# schematic.net
KiCad netlist of a schematic drawn in EAGLE
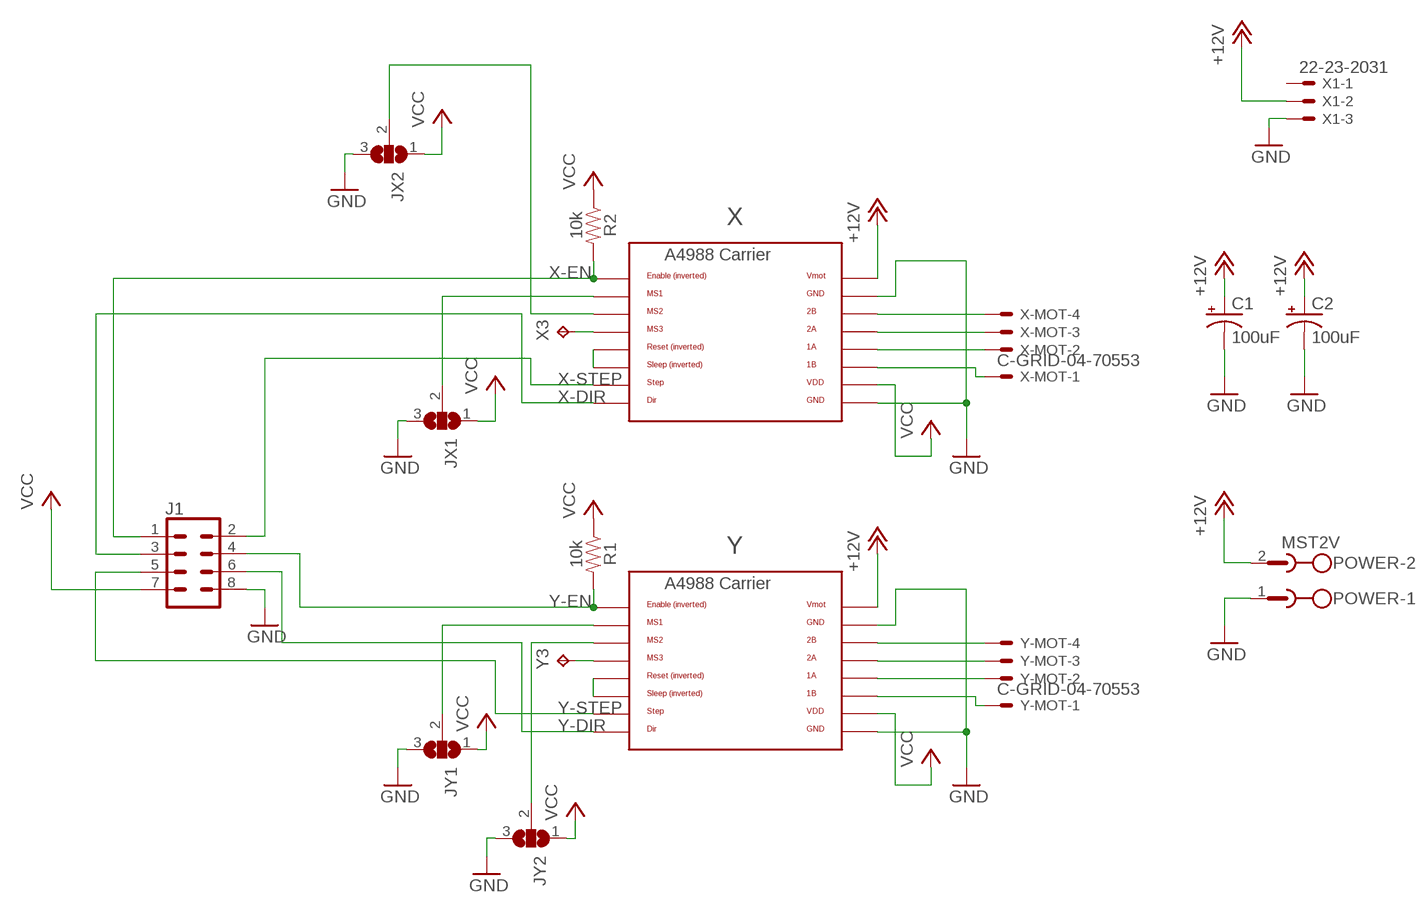
[diagram p0: schematic, sheet 1]

(export (version "E")
  (design (tool "Eeschema 10.0.6"))
  (components
    (comp (ref "C1")
      (value "100uF")
      (footprint "eagle-import:CPOL-RADIAL-2.5MM-6.5MM")
      (libsource (lib "eagle-import") (part "100UF-POLAR-RADIAL-2.5MM-25V-20%"))
    )
    (comp (ref "C2")
      (value "100uF")
      (footprint "eagle-import:CPOL-RADIAL-2.5MM-6.5MM")
      (libsource (lib "eagle-import") (part "100UF-POLAR-RADIAL-2.5MM-25V-20%"))
    )
    (comp (ref "J1")
      (value "CONN_04X2")
      (footprint "eagle-import:2X4")
      (libsource (lib "eagle-import") (part "CONN_04X2"))
    )
    (comp (ref "JX1")
      (value "SJ2W")
      (footprint "eagle-import:SJ_2")
      (libsource (lib "eagle-import") (part "SJ2W"))
    )
    (comp (ref "JX2")
      (value "SJ2W")
      (footprint "eagle-import:SJ_2")
      (libsource (lib "eagle-import") (part "SJ2W"))
    )
    (comp (ref "JY1")
      (value "SJ2W")
      (footprint "eagle-import:SJ_2")
      (libsource (lib "eagle-import") (part "SJ2W"))
    )
    (comp (ref "JY2")
      (value "SJ2W")
      (footprint "eagle-import:SJ_2")
      (libsource (lib "eagle-import") (part "SJ2W"))
    )
    (comp (ref "POWER")
      (value "MST2V")
      (footprint "eagle-import:MSTBV2")
      (libsource (lib "eagle-import") (part "MST2V"))
    )
    (comp (ref "R1")
      (value "10k")
      (footprint "eagle-import:AXIAL-0.3")
      (libsource (lib "eagle-import") (part "10KOHM-HORIZ-1/4W-1%"))
    )
    (comp (ref "R2")
      (value "10k")
      (footprint "eagle-import:AXIAL-0.3")
      (libsource (lib "eagle-import") (part "10KOHM-HORIZ-1/4W-1%"))
    )
    (comp (ref "U$1")
      (value "A4988BREAKOUT")
      (footprint "eagle-import:A4988BREAKOUT")
      (libsource (lib "eagle-import") (part "A4988BREAKOUT"))
    )
    (comp (ref "U$4")
      (value "A4988BREAKOUT")
      (footprint "eagle-import:A4988BREAKOUT")
      (libsource (lib "eagle-import") (part "A4988BREAKOUT"))
    )
    (comp (ref "X-MOT")
      (value "C-GRID-04-70553")
      (footprint "eagle-import:70553-04")
      (libsource (lib "eagle-import") (part "C-GRID-04-70553"))
    )
    (comp (ref "X1")
      (value "22-23-2031")
      (footprint "eagle-import:22-23-2031")
      (fields (field (name "MF") "MOLEX"))
      (libsource (lib "eagle-import") (part "22-23-2031"))
    )
    (comp (ref "X3")
      (value "TPB1,27")
      (footprint "eagle-import:B1,27")
      (libsource (lib "eagle-import") (part "TPB1,27"))
    )
    (comp (ref "Y-MOT")
      (value "C-GRID-04-70553")
      (footprint "eagle-import:70553-04")
      (libsource (lib "eagle-import") (part "C-GRID-04-70553"))
    )
    (comp (ref "Y3")
      (value "TPB1,27")
      (footprint "eagle-import:B1,27")
      (libsource (lib "eagle-import") (part "TPB1,27"))
    )
  )
  (nets
    (net (code "1") (name "+12V") (class "Default")
      (node (ref "C1") (pin "1") (pinfunction "+_1") (pintype "passive"))
      (node (ref "C2") (pin "1") (pinfunction "+_1") (pintype "passive"))
      (node (ref "POWER") (pin "2") (pinfunction "1_2") (pintype "passive"))
      (node (ref "U$1") (pin "VMOT") (pinfunction "VMOT_VMOT") (pintype "power_in"))
      (node (ref "U$4") (pin "VMOT") (pinfunction "VMOT_VMOT") (pintype "power_in"))
      (node (ref "X1") (pin "2") (pinfunction "S_2") (pintype "passive"))
    )
    (net (code "2") (name "/X-DIR") (class "Default")
      (node (ref "J1") (pin "3") (pinfunction "3_3") (pintype "passive"))
      (node (ref "U$1") (pin "DIR") (pinfunction "DIR_DIR") (pintype "input"))
    )
    (net (code "3") (name "/X-EN") (class "Default")
      (node (ref "J1") (pin "1") (pinfunction "1_1") (pintype "passive"))
      (node (ref "R2") (pin "P$2") (pinfunction "2_P$2") (pintype "passive"))
      (node (ref "U$1") (pin "EN") (pinfunction "EN_EN") (pintype "input"))
    )
    (net (code "4") (name "/X-STEP") (class "Default")
      (node (ref "J1") (pin "2") (pinfunction "2_2") (pintype "passive"))
      (node (ref "U$1") (pin "STEP") (pinfunction "STEP_STEP") (pintype "input"))
    )
    (net (code "5") (name "/Y-DIR") (class "Default")
      (node (ref "J1") (pin "6") (pinfunction "6_6") (pintype "passive"))
      (node (ref "U$4") (pin "DIR") (pinfunction "DIR_DIR") (pintype "input"))
    )
    (net (code "6") (name "/Y-EN") (class "Default")
      (node (ref "J1") (pin "4") (pinfunction "4_4") (pintype "passive"))
      (node (ref "R1") (pin "P$2") (pinfunction "2_P$2") (pintype "passive"))
      (node (ref "U$4") (pin "EN") (pinfunction "EN_EN") (pintype "input"))
    )
    (net (code "7") (name "/Y-STEP") (class "Default")
      (node (ref "J1") (pin "5") (pinfunction "5_5") (pintype "passive"))
      (node (ref "U$4") (pin "STEP") (pinfunction "STEP_STEP") (pintype "input"))
    )
    (net (code "8") (name "GND") (class "Default")
      (node (ref "C1") (pin "2") (pinfunction "-_2") (pintype "passive"))
      (node (ref "C2") (pin "2") (pinfunction "-_2") (pintype "passive"))
      (node (ref "J1") (pin "8") (pinfunction "8_8") (pintype "passive"))
      (node (ref "JX1") (pin "3") (pinfunction "3_3") (pintype "passive"))
      (node (ref "JX2") (pin "3") (pinfunction "3_3") (pintype "passive"))
      (node (ref "JY1") (pin "3") (pinfunction "3_3") (pintype "passive"))
      (node (ref "JY2") (pin "3") (pinfunction "3_3") (pintype "passive"))
      (node (ref "POWER") (pin "1") (pinfunction "1_1") (pintype "passive"))
      (node (ref "U$1") (pin "GND") (pinfunction "GND_GND") (pintype "power_in"))
      (node (ref "U$1") (pin "GND@0") (pinfunction "GND_GND@0") (pintype "power_in"))
      (node (ref "U$4") (pin "GND") (pinfunction "GND_GND") (pintype "power_in"))
      (node (ref "U$4") (pin "GND@0") (pinfunction "GND_GND@0") (pintype "power_in"))
      (node (ref "X1") (pin "3") (pinfunction "S_3") (pintype "passive"))
    )
    (net (code "9") (name "Net-(JX1-Pad2)") (class "Default")
      (node (ref "JX1") (pin "2") (pinfunction "2_2") (pintype "passive"))
      (node (ref "U$1") (pin "MS1") (pinfunction "MS1_MS1") (pintype "input"))
    )
    (net (code "10") (name "Net-(JX2-Pad2)") (class "Default")
      (node (ref "JX2") (pin "2") (pinfunction "2_2") (pintype "passive"))
      (node (ref "U$1") (pin "MS2") (pinfunction "MS2_MS2") (pintype "input"))
    )
    (net (code "11") (name "Net-(JY1-Pad2)") (class "Default")
      (node (ref "JY1") (pin "2") (pinfunction "2_2") (pintype "passive"))
      (node (ref "U$4") (pin "MS1") (pinfunction "MS1_MS1") (pintype "input"))
    )
    (net (code "12") (name "Net-(JY2-Pad2)") (class "Default")
      (node (ref "JY2") (pin "2") (pinfunction "2_2") (pintype "passive"))
      (node (ref "U$4") (pin "MS2") (pinfunction "MS2_MS2") (pintype "input"))
    )
    (net (code "13") (name "Net-(U$1-PadMS3)") (class "Default")
      (node (ref "U$1") (pin "MS3") (pinfunction "MS3_MS3") (pintype "input"))
      (node (ref "X3") (pin "TP") (pinfunction "TP_TP") (pintype "input"))
    )
    (net (code "14") (name "Net-(U$1-SLEEP)") (class "Default")
      (node (ref "U$1") (pin "RST") (pinfunction "RST_RST") (pintype "input"))
      (node (ref "U$1") (pin "SLP") (pinfunction "SLEEP_SLP") (pintype "input"))
    )
    (net (code "15") (name "Net-(U$4-PadMS3)") (class "Default")
      (node (ref "U$4") (pin "MS3") (pinfunction "MS3_MS3") (pintype "input"))
      (node (ref "Y3") (pin "TP") (pinfunction "TP_TP") (pintype "input"))
    )
    (net (code "16") (name "Net-(U$4-SLEEP)") (class "Default")
      (node (ref "U$4") (pin "RST") (pinfunction "RST_RST") (pintype "input"))
      (node (ref "U$4") (pin "SLP") (pinfunction "SLEEP_SLP") (pintype "input"))
    )
    (net (code "17") (name "Net-(X-MOTA-S)") (class "Default")
      (node (ref "U$1") (pin "1B") (pinfunction "1B_1B") (pintype "output"))
      (node (ref "X-MOT") (pin "1") (pinfunction "S_1") (pintype "passive"))
    )
    (net (code "18") (name "Net-(X-MOTB-S)") (class "Default")
      (node (ref "U$1") (pin "1A") (pinfunction "1A_1A") (pintype "output"))
      (node (ref "X-MOT") (pin "2") (pinfunction "S_2") (pintype "passive"))
    )
    (net (code "19") (name "Net-(X-MOTC-S)") (class "Default")
      (node (ref "U$1") (pin "2A") (pinfunction "2A_2A") (pintype "output"))
      (node (ref "X-MOT") (pin "3") (pinfunction "S_3") (pintype "passive"))
    )
    (net (code "20") (name "Net-(X-MOTD-S)") (class "Default")
      (node (ref "U$1") (pin "2B") (pinfunction "2B_2B") (pintype "output"))
      (node (ref "X-MOT") (pin "4") (pinfunction "S_4") (pintype "passive"))
    )
    (net (code "21") (name "Net-(Y-MOTA-S)") (class "Default")
      (node (ref "U$4") (pin "1B") (pinfunction "1B_1B") (pintype "output"))
      (node (ref "Y-MOT") (pin "1") (pinfunction "S_1") (pintype "passive"))
    )
    (net (code "22") (name "Net-(Y-MOTB-S)") (class "Default")
      (node (ref "U$4") (pin "1A") (pinfunction "1A_1A") (pintype "output"))
      (node (ref "Y-MOT") (pin "2") (pinfunction "S_2") (pintype "passive"))
    )
    (net (code "23") (name "Net-(Y-MOTC-S)") (class "Default")
      (node (ref "U$4") (pin "2A") (pinfunction "2A_2A") (pintype "output"))
      (node (ref "Y-MOT") (pin "3") (pinfunction "S_3") (pintype "passive"))
    )
    (net (code "24") (name "Net-(Y-MOTD-S)") (class "Default")
      (node (ref "U$4") (pin "2B") (pinfunction "2B_2B") (pintype "output"))
      (node (ref "Y-MOT") (pin "4") (pinfunction "S_4") (pintype "passive"))
    )
    (net (code "25") (name "VCC") (class "Default")
      (node (ref "J1") (pin "7") (pinfunction "7_7") (pintype "passive"))
      (node (ref "JX1") (pin "1") (pinfunction "1_1") (pintype "passive"))
      (node (ref "JX2") (pin "1") (pinfunction "1_1") (pintype "passive"))
      (node (ref "JY1") (pin "1") (pinfunction "1_1") (pintype "passive"))
      (node (ref "JY2") (pin "1") (pinfunction "1_1") (pintype "passive"))
      (node (ref "R1") (pin "P$1") (pinfunction "1_P$1") (pintype "passive"))
      (node (ref "R2") (pin "P$1") (pinfunction "1_P$1") (pintype "passive"))
      (node (ref "U$1") (pin "VDD") (pinfunction "VDD_VDD") (pintype "power_in"))
      (node (ref "U$4") (pin "VDD") (pinfunction "VDD_VDD") (pintype "power_in"))
    )
    (net (code "26") (name "unconnected-(X1A-S-Pad1)") (class "Default")
      (node (ref "X1") (pin "1") (pinfunction "S_1") (pintype "passive"))
    )
  )
)
